# Wakeup_Transmitter.net
KiCad netlist of a schematic drawn in EasyEDA
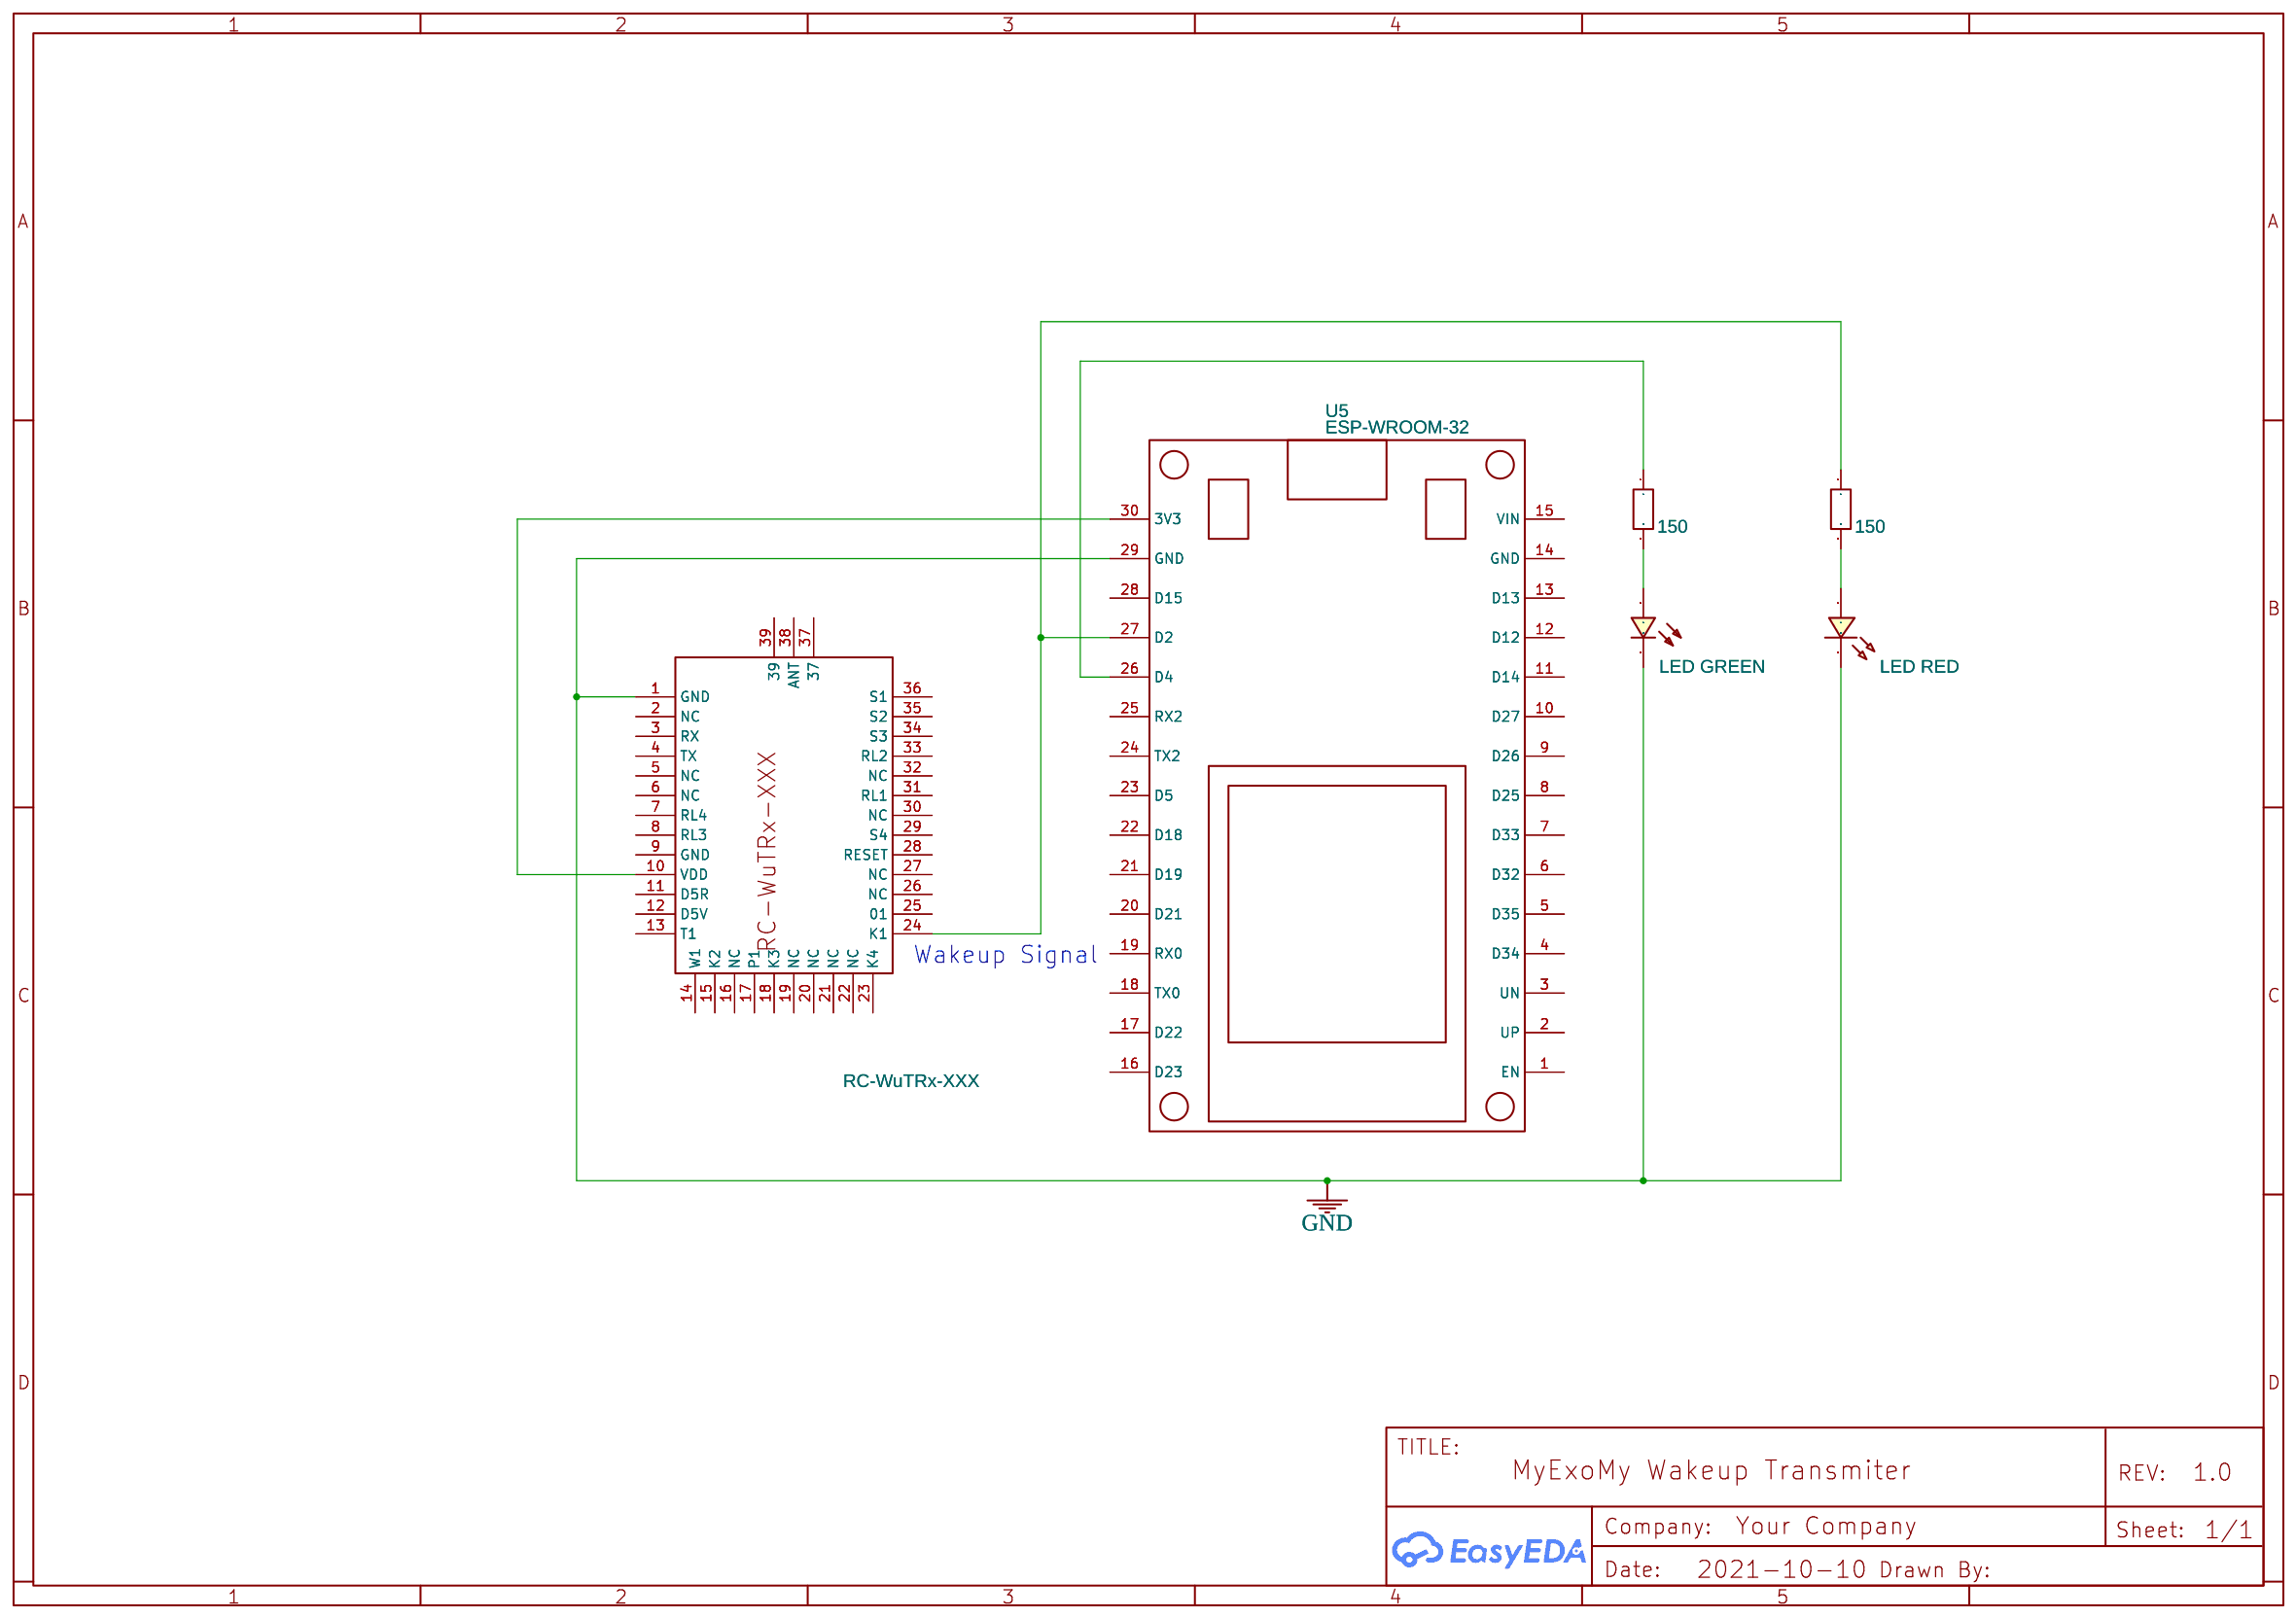
[diagram p0: schematic sheet]

(export (version "E")
  (design (tool "Eeschema 10.0.6"))
  (components
    (comp (ref "1") (value "LED GREEN") (libsource (lib "") (part "LED GREEN D4")))
    (comp (ref "LED1")
      (value "LED RED")
      (fields
        (field (name "BOM_Manufacturer Part") "19-217/R6C-AL1M2VY/3T")
        (field (name "BOM_Supplier Part") "C72044")
      )
      (libsource (lib "") (part "LED-0603_R"))
    )
    (comp (ref "R15") (value "150") (libsource (lib "") (part "R_0603_EU")))
    (comp (ref "R16") (value "150") (libsource (lib "") (part "R_0603_EU")))
    (comp (ref "U5")
      (value "ESP-WROOM-32")
      (fields (field (name "BOM_Manufacturer Part") "ESP32 Development Board"))
      (libsource (lib "") (part "ESP-WROOM-32"))
    )
    (comp (ref "U7") (value "RC-WuTRx-XXX") (libsource (lib "") (part "RC-WuTRx-XXX")))
  )
  (nets
    (net (code "1") (name "GND") (class "Default")
      (node (ref "1") (pin "2") (pinfunction "2_2") (pintype "input"))
      (node (ref "LED1") (pin "2") (pinfunction "2_2") (pintype "unspecified"))
      (node (ref "U5") (pin "29") (pinfunction "GND_29") (pintype "bidirectional"))
      (node (ref "U7") (pin "1") (pinfunction "GND_1") (pintype "unspecified"))
    )
    (net (code "2") (name "Net-(1-Pad1)") (class "Default")
      (node (ref "1") (pin "1") (pinfunction "1_1") (pintype "input"))
      (node (ref "R15") (pin "2") (pinfunction "2_2") (pintype "unspecified"))
    )
    (net (code "3") (name "Net-(LED1-Pad1)") (class "Default")
      (node (ref "LED1") (pin "1") (pinfunction "1_1") (pintype "unspecified"))
      (node (ref "R16") (pin "2") (pinfunction "2_2") (pintype "unspecified"))
    )
    (net (code "4") (name "Net-(U5-3V3)") (class "Default")
      (node (ref "U5") (pin "30") (pinfunction "3V3_30") (pintype "bidirectional"))
      (node (ref "U7") (pin "10") (pinfunction "VDD_10") (pintype "unspecified"))
    )
    (net (code "5") (name "Net-(U5-D2)") (class "Default")
      (node (ref "R16") (pin "1") (pinfunction "1_1") (pintype "unspecified"))
      (node (ref "U5") (pin "27") (pinfunction "D2_27") (pintype "bidirectional"))
      (node (ref "U7") (pin "24") (pinfunction "K1_24") (pintype "unspecified"))
    )
    (net (code "6") (name "Net-(U5-D4)") (class "Default")
      (node (ref "R15") (pin "1") (pinfunction "1_1") (pintype "unspecified"))
      (node (ref "U5") (pin "26") (pinfunction "D4_26") (pintype "bidirectional"))
    )
    (net (code "7") (name "unconnected-(U5-D5-Pad23)") (class "Default")
      (node (ref "U5") (pin "23") (pinfunction "D5_23") (pintype "bidirectional"))
    )
    (net (code "8") (name "unconnected-(U5-D12-Pad12)") (class "Default")
      (node (ref "U5") (pin "12") (pinfunction "D12_12") (pintype "bidirectional"))
    )
    (net (code "9") (name "unconnected-(U5-D13-Pad13)") (class "Default")
      (node (ref "U5") (pin "13") (pinfunction "D13_13") (pintype "bidirectional"))
    )
    (net (code "10") (name "unconnected-(U5-D14-Pad11)") (class "Default")
      (node (ref "U5") (pin "11") (pinfunction "D14_11") (pintype "bidirectional"))
    )
    (net (code "11") (name "unconnected-(U5-D15-Pad28)") (class "Default")
      (node (ref "U5") (pin "28") (pinfunction "D15_28") (pintype "bidirectional"))
    )
    (net (code "12") (name "unconnected-(U5-D18-Pad22)") (class "Default")
      (node (ref "U5") (pin "22") (pinfunction "D18_22") (pintype "passive"))
    )
    (net (code "13") (name "unconnected-(U5-D19-Pad21)") (class "Default")
      (node (ref "U5") (pin "21") (pinfunction "D19_21") (pintype "bidirectional"))
    )
    (net (code "14") (name "unconnected-(U5-D21-Pad20)") (class "Default")
      (node (ref "U5") (pin "20") (pinfunction "D21_20") (pintype "bidirectional"))
    )
    (net (code "15") (name "unconnected-(U5-D22-Pad17)") (class "Default")
      (node (ref "U5") (pin "17") (pinfunction "D22_17") (pintype "bidirectional"))
    )
    (net (code "16") (name "unconnected-(U5-D23-Pad16)") (class "Default")
      (node (ref "U5") (pin "16") (pinfunction "D23_16") (pintype "passive"))
    )
    (net (code "17") (name "unconnected-(U5-D25-Pad8)") (class "Default")
      (node (ref "U5") (pin "8") (pinfunction "D25_8") (pintype "bidirectional"))
    )
    (net (code "18") (name "unconnected-(U5-D26-Pad9)") (class "Default")
      (node (ref "U5") (pin "9") (pinfunction "D26_9") (pintype "bidirectional"))
    )
    (net (code "19") (name "unconnected-(U5-D27-Pad10)") (class "Default")
      (node (ref "U5") (pin "10") (pinfunction "D27_10") (pintype "bidirectional"))
    )
    (net (code "20") (name "unconnected-(U5-D32-Pad6)") (class "Default")
      (node (ref "U5") (pin "6") (pinfunction "D32_6") (pintype "bidirectional"))
    )
    (net (code "21") (name "unconnected-(U5-D33-Pad7)") (class "Default")
      (node (ref "U5") (pin "7") (pinfunction "D33_7") (pintype "bidirectional"))
    )
    (net (code "22") (name "unconnected-(U5-D34-Pad4)") (class "Default")
      (node (ref "U5") (pin "4") (pinfunction "D34_4") (pintype "bidirectional"))
    )
    (net (code "23") (name "unconnected-(U5-D35-Pad5)") (class "Default")
      (node (ref "U5") (pin "5") (pinfunction "D35_5") (pintype "bidirectional"))
    )
    (net (code "24") (name "unconnected-(U5-EN-Pad1)") (class "Default")
      (node (ref "U5") (pin "1") (pinfunction "EN_1") (pintype "passive"))
    )
    (net (code "25") (name "unconnected-(U5-GND-Pad14)") (class "Default")
      (node (ref "U5") (pin "14") (pinfunction "GND_14") (pintype "passive"))
    )
    (net (code "26") (name "unconnected-(U5-RX0-Pad19)") (class "Default")
      (node (ref "U5") (pin "19") (pinfunction "RX0_19") (pintype "bidirectional"))
    )
    (net (code "27") (name "unconnected-(U5-RX2-Pad25)") (class "Default")
      (node (ref "U5") (pin "25") (pinfunction "RX2_25") (pintype "bidirectional"))
    )
    (net (code "28") (name "unconnected-(U5-TX0-Pad18)") (class "Default")
      (node (ref "U5") (pin "18") (pinfunction "TX0_18") (pintype "bidirectional"))
    )
    (net (code "29") (name "unconnected-(U5-TX2-Pad24)") (class "Default")
      (node (ref "U5") (pin "24") (pinfunction "TX2_24") (pintype "bidirectional"))
    )
    (net (code "30") (name "unconnected-(U5-UN-Pad3)") (class "Default")
      (node (ref "U5") (pin "3") (pinfunction "UN_3") (pintype "bidirectional"))
    )
    (net (code "31") (name "unconnected-(U5-UP-Pad2)") (class "Default")
      (node (ref "U5") (pin "2") (pinfunction "UP_2") (pintype "bidirectional"))
    )
    (net (code "32") (name "unconnected-(U5-VIN-Pad15)") (class "Default")
      (node (ref "U5") (pin "15") (pinfunction "VIN_15") (pintype "bidirectional"))
    )
    (net (code "33") (name "unconnected-(U7-01-Pad25)") (class "Default")
      (node (ref "U7") (pin "25") (pinfunction "01_25") (pintype "unspecified"))
    )
    (net (code "34") (name "unconnected-(U7-ANT-Pad38)") (class "Default")
      (node (ref "U7") (pin "38") (pinfunction "ANT_38") (pintype "unspecified"))
    )
    (net (code "35") (name "unconnected-(U7-D5R-Pad11)") (class "Default")
      (node (ref "U7") (pin "11") (pinfunction "D5R_11") (pintype "unspecified"))
    )
    (net (code "36") (name "unconnected-(U7-D5V-Pad12)") (class "Default")
      (node (ref "U7") (pin "12") (pinfunction "D5V_12") (pintype "unspecified"))
    )
    (net (code "37") (name "unconnected-(U7-GND-Pad9)") (class "Default")
      (node (ref "U7") (pin "9") (pinfunction "GND_9") (pintype "unspecified"))
    )
    (net (code "38") (name "unconnected-(U7-K2-Pad15)") (class "Default")
      (node (ref "U7") (pin "15") (pinfunction "K2_15") (pintype "unspecified"))
    )
    (net (code "39") (name "unconnected-(U7-K3-Pad18)") (class "Default")
      (node (ref "U7") (pin "18") (pinfunction "K3_18") (pintype "unspecified"))
    )
    (net (code "40") (name "unconnected-(U7-K4-Pad23)") (class "Default")
      (node (ref "U7") (pin "23") (pinfunction "K4_23") (pintype "unspecified"))
    )
    (net (code "41") (name "unconnected-(U7-NC-Pad2)") (class "Default")
      (node (ref "U7") (pin "2") (pinfunction "NC_2") (pintype "unspecified"))
    )
    (net (code "42") (name "unconnected-(U7-NC-Pad5)") (class "Default")
      (node (ref "U7") (pin "5") (pinfunction "NC_5") (pintype "unspecified"))
    )
    (net (code "43") (name "unconnected-(U7-NC-Pad6)") (class "Default")
      (node (ref "U7") (pin "6") (pinfunction "NC_6") (pintype "unspecified"))
    )
    (net (code "44") (name "unconnected-(U7-NC-Pad16)") (class "Default")
      (node (ref "U7") (pin "16") (pinfunction "NC_16") (pintype "unspecified"))
    )
    (net (code "45") (name "unconnected-(U7-NC-Pad19)") (class "Default")
      (node (ref "U7") (pin "19") (pinfunction "NC_19") (pintype "unspecified"))
    )
    (net (code "46") (name "unconnected-(U7-NC-Pad20)") (class "Default")
      (node (ref "U7") (pin "20") (pinfunction "NC_20") (pintype "unspecified"))
    )
    (net (code "47") (name "unconnected-(U7-NC-Pad21)") (class "Default")
      (node (ref "U7") (pin "21") (pinfunction "NC_21") (pintype "unspecified"))
    )
    (net (code "48") (name "unconnected-(U7-NC-Pad22)") (class "Default")
      (node (ref "U7") (pin "22") (pinfunction "NC_22") (pintype "unspecified"))
    )
    (net (code "49") (name "unconnected-(U7-NC-Pad26)") (class "Default")
      (node (ref "U7") (pin "26") (pinfunction "NC_26") (pintype "unspecified"))
    )
    (net (code "50") (name "unconnected-(U7-NC-Pad27)") (class "Default")
      (node (ref "U7") (pin "27") (pinfunction "NC_27") (pintype "unspecified"))
    )
    (net (code "51") (name "unconnected-(U7-NC-Pad30)") (class "Default")
      (node (ref "U7") (pin "30") (pinfunction "NC_30") (pintype "unspecified"))
    )
    (net (code "52") (name "unconnected-(U7-NC-Pad32)") (class "Default")
      (node (ref "U7") (pin "32") (pinfunction "NC_32") (pintype "unspecified"))
    )
    (net (code "53") (name "unconnected-(U7-P1-Pad17)") (class "Default")
      (node (ref "U7") (pin "17") (pinfunction "P1_17") (pintype "unspecified"))
    )
    (net (code "54") (name "unconnected-(U7-Pad37)") (class "Default")
      (node (ref "U7") (pin "37") (pinfunction "37_37") (pintype "unspecified"))
    )
    (net (code "55") (name "unconnected-(U7-Pad39)") (class "Default")
      (node (ref "U7") (pin "39") (pinfunction "39_39") (pintype "unspecified"))
    )
    (net (code "56") (name "unconnected-(U7-RESET-Pad28)") (class "Default")
      (node (ref "U7") (pin "28") (pinfunction "RESET_28") (pintype "unspecified"))
    )
    (net (code "57") (name "unconnected-(U7-RL1-Pad31)") (class "Default")
      (node (ref "U7") (pin "31") (pinfunction "RL1_31") (pintype "unspecified"))
    )
    (net (code "58") (name "unconnected-(U7-RL2-Pad33)") (class "Default")
      (node (ref "U7") (pin "33") (pinfunction "RL2_33") (pintype "unspecified"))
    )
    (net (code "59") (name "unconnected-(U7-RL3-Pad8)") (class "Default")
      (node (ref "U7") (pin "8") (pinfunction "RL3_8") (pintype "unspecified"))
    )
    (net (code "60") (name "unconnected-(U7-RL4-Pad7)") (class "Default")
      (node (ref "U7") (pin "7") (pinfunction "RL4_7") (pintype "unspecified"))
    )
    (net (code "61") (name "unconnected-(U7-RX-Pad3)") (class "Default")
      (node (ref "U7") (pin "3") (pinfunction "RX_3") (pintype "unspecified"))
    )
    (net (code "62") (name "unconnected-(U7-S1-Pad36)") (class "Default")
      (node (ref "U7") (pin "36") (pinfunction "S1_36") (pintype "unspecified"))
    )
    (net (code "63") (name "unconnected-(U7-S2-Pad35)") (class "Default")
      (node (ref "U7") (pin "35") (pinfunction "S2_35") (pintype "unspecified"))
    )
    (net (code "64") (name "unconnected-(U7-S3-Pad34)") (class "Default")
      (node (ref "U7") (pin "34") (pinfunction "S3_34") (pintype "unspecified"))
    )
    (net (code "65") (name "unconnected-(U7-S4-Pad29)") (class "Default")
      (node (ref "U7") (pin "29") (pinfunction "S4_29") (pintype "unspecified"))
    )
    (net (code "66") (name "unconnected-(U7-T1-Pad13)") (class "Default")
      (node (ref "U7") (pin "13") (pinfunction "T1_13") (pintype "unspecified"))
    )
    (net (code "67") (name "unconnected-(U7-TX-Pad4)") (class "Default")
      (node (ref "U7") (pin "4") (pinfunction "TX_4") (pintype "unspecified"))
    )
    (net (code "68") (name "unconnected-(U7-W1-Pad14)") (class "Default")
      (node (ref "U7") (pin "14") (pinfunction "W1_14") (pintype "unspecified"))
    )
  )
)
